# LCD_Ohmmeter.net
KiCad netlist of a schematic drawn in Altium Designer
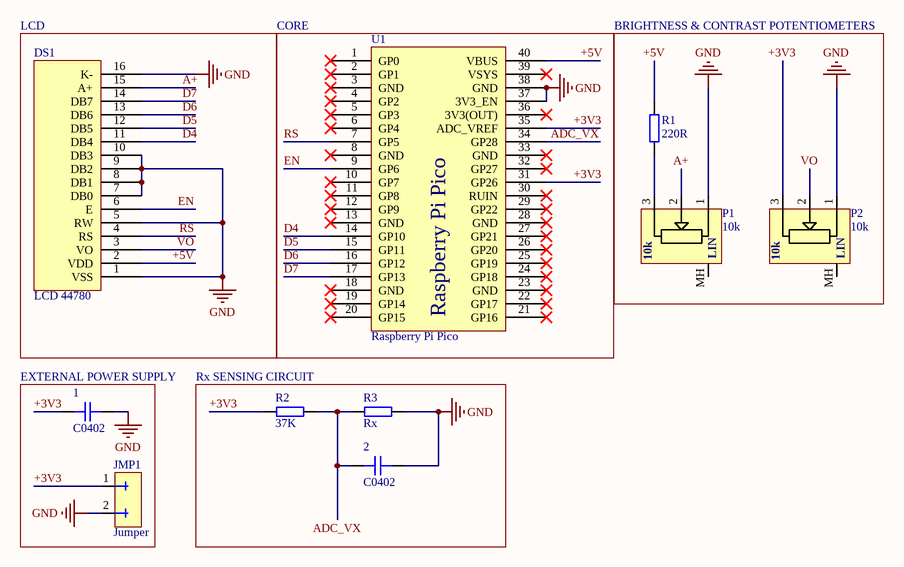
[diagram p0: LCD Ohmmeter.SchDoc]

(export (version "E")
  (design (tool "Eeschema 10.0.6"))
  (components
    (comp (ref "1")
      (value "C0402")
      (footprint "CAP_0402")
      (description "Capacitor SMD 0402")
      (libsource (lib "Schematic-Lib-PhilsLab") (part "CAP_0402"))
    )
    (comp (ref "2")
      (value "C0402")
      (footprint "CAP_0402")
      (description "Capacitor SMD 0402")
      (libsource (lib "Schematic-Lib-PhilsLab") (part "CAP_0402"))
    )
    (comp (ref "DS1")
      (value "LCD 44780")
      (footprint "OLED 16x2")
      (libsource (lib "ECE Lib 22") (part "LCD 44780"))
    )
    (comp (ref "JMP1")
      (value "Jumper")
      (footprint "JMP2_TH")
      (description "Jumper 2 Pins Through-Hole DO NOT PLACE")
      (libsource (lib "Schematic-Lib-PhilsLab") (part "JMP2_TH"))
    )
    (comp (ref "P1")
      (value "10k")
      (footprint "RK09L1140A5L")
      (description "Potentiometer Vertical 10k Linear Taper (1B) THT PCB-Mount D-Type 6mm Shaft")
      (fields
        (field (name "MANUFACTURER") "Alps Alpine")
        (field (name "MANUFACTURER PART NUMBER") "RK09L1140A5L")
      )
      (libsource (lib "Schematic-Lib-PhilsLab") (part "RK09L1140A5L"))
    )
    (comp (ref "P2")
      (value "10k")
      (footprint "RK09L1140A5L")
      (description "Potentiometer Vertical 10k Linear Taper (1B) THT PCB-Mount D-Type 6mm Shaft")
      (fields
        (field (name "MANUFACTURER") "Alps Alpine")
        (field (name "MANUFACTURER PART NUMBER") "RK09L1140A5L")
      )
      (libsource (lib "Schematic-Lib-PhilsLab") (part "RK09L1140A5L"))
    )
    (comp (ref "R1")
      (value "220R")
      (footprint "RES_0402")
      (description "Resistor SMD 0402")
      (libsource (lib "Schematic-Lib-PhilsLab") (part "RES_0402"))
    )
    (comp (ref "R2")
      (value "37K")
      (footprint "RES_0402")
      (description "Resistor SMD 0402")
      (libsource (lib "Schematic-Lib-PhilsLab") (part "RES_0402"))
    )
    (comp (ref "R3")
      (value "Rx")
      (footprint "RES_0402")
      (description "Resistor SMD 0402")
      (libsource (lib "Schematic-Lib-PhilsLab") (part "RES_0402"))
    )
    (comp (ref "U1")
      (value "Raspberry Pi Pico")
      (footprint "Raspberry Pi Pico")
      (libsource (lib "ECE Lib 22") (part "Raspberry Pi Pico"))
    )
  )
  (nets
    (net (code "1") (name "/+3V3") (class "Default")
      (node (ref "1") (pin "1") (pinfunction "1_1") (pintype "passive"))
      (node (ref "JMP1") (pin "1") (pinfunction "1_1") (pintype "passive"))
      (node (ref "P2") (pin "3") (pinfunction "3_3") (pintype "passive"))
      (node (ref "R2") (pin "2") (pinfunction "2_2") (pintype "passive"))
      (node (ref "U1") (pin "31") (pinfunction "GP26_31") (pintype "passive"))
      (node (ref "U1") (pin "35") (pinfunction "ADC_VREF_35") (pintype "passive"))
    )
    (net (code "2") (name "/+5V") (class "Default")
      (node (ref "DS1") (pin "2") (pinfunction "VDD_2") (pintype "passive"))
      (node (ref "R1") (pin "2") (pinfunction "2_2") (pintype "passive"))
      (node (ref "U1") (pin "40") (pinfunction "VBUS_40") (pintype "passive"))
    )
    (net (code "3") (name "/A+") (class "Default")
      (node (ref "DS1") (pin "15") (pinfunction "A+_15") (pintype "passive"))
      (node (ref "P1") (pin "2") (pinfunction "2_2") (pintype "passive"))
    )
    (net (code "4") (name "/ADC_VX") (class "Default")
      (node (ref "2") (pin "1") (pinfunction "1_1") (pintype "passive"))
      (node (ref "R2") (pin "1") (pinfunction "1_1") (pintype "passive"))
      (node (ref "R3") (pin "2") (pinfunction "2_2") (pintype "passive"))
      (node (ref "U1") (pin "34") (pinfunction "GP28_34") (pintype "passive"))
    )
    (net (code "5") (name "/D4") (class "Default")
      (node (ref "DS1") (pin "11") (pinfunction "DB4_11") (pintype "passive"))
      (node (ref "U1") (pin "14") (pinfunction "GP10_14") (pintype "passive"))
    )
    (net (code "6") (name "/D5") (class "Default")
      (node (ref "DS1") (pin "12") (pinfunction "DB5_12") (pintype "passive"))
      (node (ref "U1") (pin "15") (pinfunction "GP11_15") (pintype "passive"))
    )
    (net (code "7") (name "/D6") (class "Default")
      (node (ref "DS1") (pin "13") (pinfunction "DB6_13") (pintype "passive"))
      (node (ref "U1") (pin "16") (pinfunction "GP12_16") (pintype "passive"))
    )
    (net (code "8") (name "/D7") (class "Default")
      (node (ref "DS1") (pin "14") (pinfunction "DB7_14") (pintype "passive"))
      (node (ref "U1") (pin "17") (pinfunction "GP13_17") (pintype "passive"))
    )
    (net (code "9") (name "/EN") (class "Default")
      (node (ref "DS1") (pin "6") (pinfunction "E_6") (pintype "passive"))
      (node (ref "U1") (pin "9") (pinfunction "GP6_9") (pintype "passive"))
    )
    (net (code "10") (name "/RS") (class "Default")
      (node (ref "DS1") (pin "4") (pinfunction "RS_4") (pintype "passive"))
      (node (ref "U1") (pin "7") (pinfunction "GP5_7") (pintype "passive"))
    )
    (net (code "11") (name "/VO") (class "Default")
      (node (ref "DS1") (pin "3") (pinfunction "VO_3") (pintype "passive"))
      (node (ref "P2") (pin "2") (pinfunction "2_2") (pintype "passive"))
    )
    (net (code "12") (name "GND") (class "Default")
      (node (ref "1") (pin "2") (pinfunction "2_2") (pintype "passive"))
      (node (ref "2") (pin "2") (pinfunction "2_2") (pintype "passive"))
      (node (ref "DS1") (pin "1") (pinfunction "VSS_1") (pintype "passive"))
      (node (ref "DS1") (pin "10") (pinfunction "DB3_10") (pintype "passive"))
      (node (ref "DS1") (pin "16") (pinfunction "K-_16") (pintype "passive"))
      (node (ref "DS1") (pin "5") (pinfunction "RW_5") (pintype "passive"))
      (node (ref "DS1") (pin "7") (pinfunction "DB0_7") (pintype "passive"))
      (node (ref "DS1") (pin "8") (pinfunction "DB1_8") (pintype "passive"))
      (node (ref "DS1") (pin "9") (pinfunction "DB2_9") (pintype "passive"))
      (node (ref "JMP1") (pin "2") (pinfunction "2_2") (pintype "passive"))
      (node (ref "P1") (pin "1") (pinfunction "1_1") (pintype "passive"))
      (node (ref "P2") (pin "1") (pinfunction "1_1") (pintype "passive"))
      (node (ref "R3") (pin "1") (pinfunction "1_1") (pintype "passive"))
      (node (ref "U1") (pin "37") (pinfunction "3V3_EN_37") (pintype "passive"))
      (node (ref "U1") (pin "38") (pinfunction "GND_38") (pintype "passive"))
    )
    (net (code "13") (name "Net-(P1-Pad3)") (class "Default")
      (node (ref "P1") (pin "3") (pinfunction "3_3") (pintype "passive"))
      (node (ref "R1") (pin "1") (pinfunction "1_1") (pintype "passive"))
    )
    (net (code "14") (name "unconnected-(P1-PadMH)") (class "Default")
      (node (ref "P1") (pin "MH") (pinfunction "MH_MH") (pintype "passive"))
    )
    (net (code "15") (name "unconnected-(P2-PadMH)") (class "Default")
      (node (ref "P2") (pin "MH") (pinfunction "MH_MH") (pintype "passive"))
    )
    (net (code "16") (name "unconnected-(U1-3V3(OUT)-Pad36)") (class "Default")
      (node (ref "U1") (pin "36") (pinfunction "3V3(OUT)_36") (pintype "passive+no_connect"))
    )
    (net (code "17") (name "unconnected-(U1-GND-Pad3)") (class "Default")
      (node (ref "U1") (pin "3") (pinfunction "GND_3") (pintype "passive+no_connect"))
    )
    (net (code "18") (name "unconnected-(U1-GND-Pad8)") (class "Default")
      (node (ref "U1") (pin "8") (pinfunction "GND_8") (pintype "passive+no_connect"))
    )
    (net (code "19") (name "unconnected-(U1-GND-Pad13)") (class "Default")
      (node (ref "U1") (pin "13") (pinfunction "GND_13") (pintype "passive+no_connect"))
    )
    (net (code "20") (name "unconnected-(U1-GND-Pad18)") (class "Default")
      (node (ref "U1") (pin "18") (pinfunction "GND_18") (pintype "passive+no_connect"))
    )
    (net (code "21") (name "unconnected-(U1-GND-Pad23)") (class "Default")
      (node (ref "U1") (pin "23") (pinfunction "GND_23") (pintype "passive+no_connect"))
    )
    (net (code "22") (name "unconnected-(U1-GND-Pad28)") (class "Default")
      (node (ref "U1") (pin "28") (pinfunction "GND_28") (pintype "passive+no_connect"))
    )
    (net (code "23") (name "unconnected-(U1-GND-Pad33)") (class "Default")
      (node (ref "U1") (pin "33") (pinfunction "GND_33") (pintype "passive+no_connect"))
    )
    (net (code "24") (name "unconnected-(U1-GP0-Pad1)") (class "Default")
      (node (ref "U1") (pin "1") (pinfunction "GP0_1") (pintype "passive+no_connect"))
    )
    (net (code "25") (name "unconnected-(U1-GP1-Pad2)") (class "Default")
      (node (ref "U1") (pin "2") (pinfunction "GP1_2") (pintype "passive+no_connect"))
    )
    (net (code "26") (name "unconnected-(U1-GP2-Pad4)") (class "Default")
      (node (ref "U1") (pin "4") (pinfunction "GP2_4") (pintype "passive+no_connect"))
    )
    (net (code "27") (name "unconnected-(U1-GP3-Pad5)") (class "Default")
      (node (ref "U1") (pin "5") (pinfunction "GP3_5") (pintype "passive+no_connect"))
    )
    (net (code "28") (name "unconnected-(U1-GP4-Pad6)") (class "Default")
      (node (ref "U1") (pin "6") (pinfunction "GP4_6") (pintype "passive+no_connect"))
    )
    (net (code "29") (name "unconnected-(U1-GP7-Pad10)") (class "Default")
      (node (ref "U1") (pin "10") (pinfunction "GP7_10") (pintype "passive+no_connect"))
    )
    (net (code "30") (name "unconnected-(U1-GP8-Pad11)") (class "Default")
      (node (ref "U1") (pin "11") (pinfunction "GP8_11") (pintype "passive+no_connect"))
    )
    (net (code "31") (name "unconnected-(U1-GP9-Pad12)") (class "Default")
      (node (ref "U1") (pin "12") (pinfunction "GP9_12") (pintype "passive+no_connect"))
    )
    (net (code "32") (name "unconnected-(U1-GP14-Pad19)") (class "Default")
      (node (ref "U1") (pin "19") (pinfunction "GP14_19") (pintype "passive+no_connect"))
    )
    (net (code "33") (name "unconnected-(U1-GP15-Pad20)") (class "Default")
      (node (ref "U1") (pin "20") (pinfunction "GP15_20") (pintype "passive+no_connect"))
    )
    (net (code "34") (name "unconnected-(U1-GP16-Pad21)") (class "Default")
      (node (ref "U1") (pin "21") (pinfunction "GP16_21") (pintype "passive+no_connect"))
    )
    (net (code "35") (name "unconnected-(U1-GP17-Pad22)") (class "Default")
      (node (ref "U1") (pin "22") (pinfunction "GP17_22") (pintype "passive+no_connect"))
    )
    (net (code "36") (name "unconnected-(U1-GP18-Pad24)") (class "Default")
      (node (ref "U1") (pin "24") (pinfunction "GP18_24") (pintype "passive+no_connect"))
    )
    (net (code "37") (name "unconnected-(U1-GP19-Pad25)") (class "Default")
      (node (ref "U1") (pin "25") (pinfunction "GP19_25") (pintype "passive+no_connect"))
    )
    (net (code "38") (name "unconnected-(U1-GP20-Pad26)") (class "Default")
      (node (ref "U1") (pin "26") (pinfunction "GP20_26") (pintype "passive+no_connect"))
    )
    (net (code "39") (name "unconnected-(U1-GP21-Pad27)") (class "Default")
      (node (ref "U1") (pin "27") (pinfunction "GP21_27") (pintype "passive+no_connect"))
    )
    (net (code "40") (name "unconnected-(U1-GP22-Pad29)") (class "Default")
      (node (ref "U1") (pin "29") (pinfunction "GP22_29") (pintype "passive+no_connect"))
    )
    (net (code "41") (name "unconnected-(U1-GP27-Pad32)") (class "Default")
      (node (ref "U1") (pin "32") (pinfunction "GP27_32") (pintype "passive+no_connect"))
    )
    (net (code "42") (name "unconnected-(U1-RUIN-Pad30)") (class "Default")
      (node (ref "U1") (pin "30") (pinfunction "RUIN_30") (pintype "passive+no_connect"))
    )
    (net (code "43") (name "unconnected-(U1-VSYS-Pad39)") (class "Default")
      (node (ref "U1") (pin "39") (pinfunction "VSYS_39") (pintype "passive+no_connect"))
    )
  )
)
